# Sheet2.net
KiCad netlist of a schematic drawn in Altium Designer
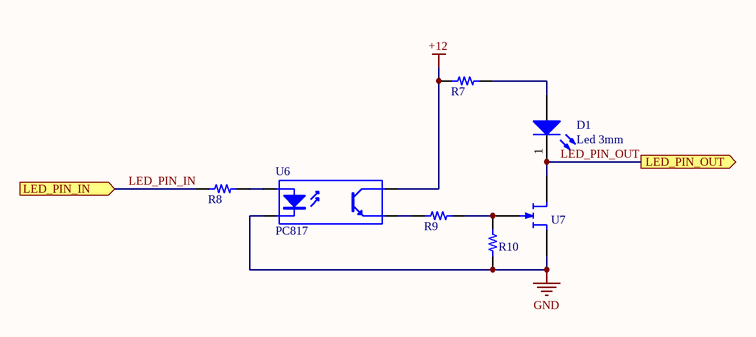
[diagram p0: Sheet2.SchDoc]

(export (version "E")
  (design (tool "Eeschema 10.0.6"))
  (components
    (comp (ref "D1")
      (value "Led 3mm")
      (footprint "LED-3mm")
      (fields (field (name "PUBLISHER") "Altium Limited"))
      (libsource (lib "URFID_8Floor_Extention") (part "LED1"))
    )
    (comp (ref "R7")
      (value "1K")
      (footprint "SMD 0805 RES")
      (libsource (lib "DIY-USB Led Controller") (part "RESISTOR"))
    )
    (comp (ref "R8")
      (value "1K")
      (footprint "SMD 0805 RES")
      (libsource (lib "DIY-USB Led Controller") (part "RESISTOR"))
    )
    (comp (ref "R9")
      (value "1K")
      (footprint "SMD 0805 RES")
      (libsource (lib "DIY-USB Led Controller") (part "RESISTOR"))
    )
    (comp (ref "R10")
      (value "1K")
      (footprint "SMD 0805 RES")
      (libsource (lib "DIY-USB Led Controller") (part "RESISTOR"))
    )
    (comp (ref "U6")
      (value "PC817")
      (footprint "OPTOISOLATOR")
      (libsource (lib "REMOTE RGBW CONTROLLER") (part "PC817"))
    )
    (comp (ref "U7")
      (value "SMD N-MOSFET")
      (footprint "DPAK228P991X238-3N")
      (libsource (lib "REMOTE RGBW CONTROLLER") (part "SMD N-MOSFET"))
    )
  )
  (nets
    (net (code "1") (name "+12") (class "Default")
      (node (ref "R7") (pin "1") (pinfunction "1_1") (pintype "passive"))
      (node (ref "U6") (pin "4") (pinfunction "C_4") (pintype "passive"))
    )
    (net (code "2") (name "/LED_PIN_IN") (class "Default")
      (node (ref "R8") (pin "1") (pinfunction "1_1") (pintype "passive"))
    )
    (net (code "3") (name "/LED_PIN_OUT") (class "Default")
      (node (ref "D1") (pin "1") (pinfunction "CATHODE_1") (pintype "passive"))
      (node (ref "U7") (pin "1") (pinfunction "D_1") (pintype "passive"))
    )
    (net (code "4") (name "GND") (class "Default")
      (node (ref "R10") (pin "1") (pinfunction "1_1") (pintype "passive"))
      (node (ref "U6") (pin "2") (pinfunction "K_2") (pintype "passive"))
      (node (ref "U7") (pin "3") (pinfunction "S_3") (pintype "passive"))
    )
    (net (code "5") (name "Net-(D1-ANODE)") (class "Default")
      (node (ref "D1") (pin "2") (pinfunction "ANODE_2") (pintype "passive"))
      (node (ref "R7") (pin "2") (pinfunction "2_2") (pintype "passive"))
    )
    (net (code "6") (name "Net-(U6-A)") (class "Default")
      (node (ref "R8") (pin "2") (pinfunction "2_2") (pintype "passive"))
      (node (ref "U6") (pin "1") (pinfunction "A_1") (pintype "passive"))
    )
    (net (code "7") (name "Net-(U6-E)") (class "Default")
      (node (ref "R9") (pin "1") (pinfunction "1_1") (pintype "passive"))
      (node (ref "U6") (pin "3") (pinfunction "E_3") (pintype "passive"))
    )
    (net (code "8") (name "Net-(U7-G)") (class "Default")
      (node (ref "R10") (pin "2") (pinfunction "2_2") (pintype "passive"))
      (node (ref "R9") (pin "2") (pinfunction "2_2") (pintype "passive"))
      (node (ref "U7") (pin "2") (pinfunction "G_2") (pintype "passive"))
    )
  )
)
